# analogTCO-RJ-alone-ext.net
KiCad netlist of a schematic drawn in EAGLE
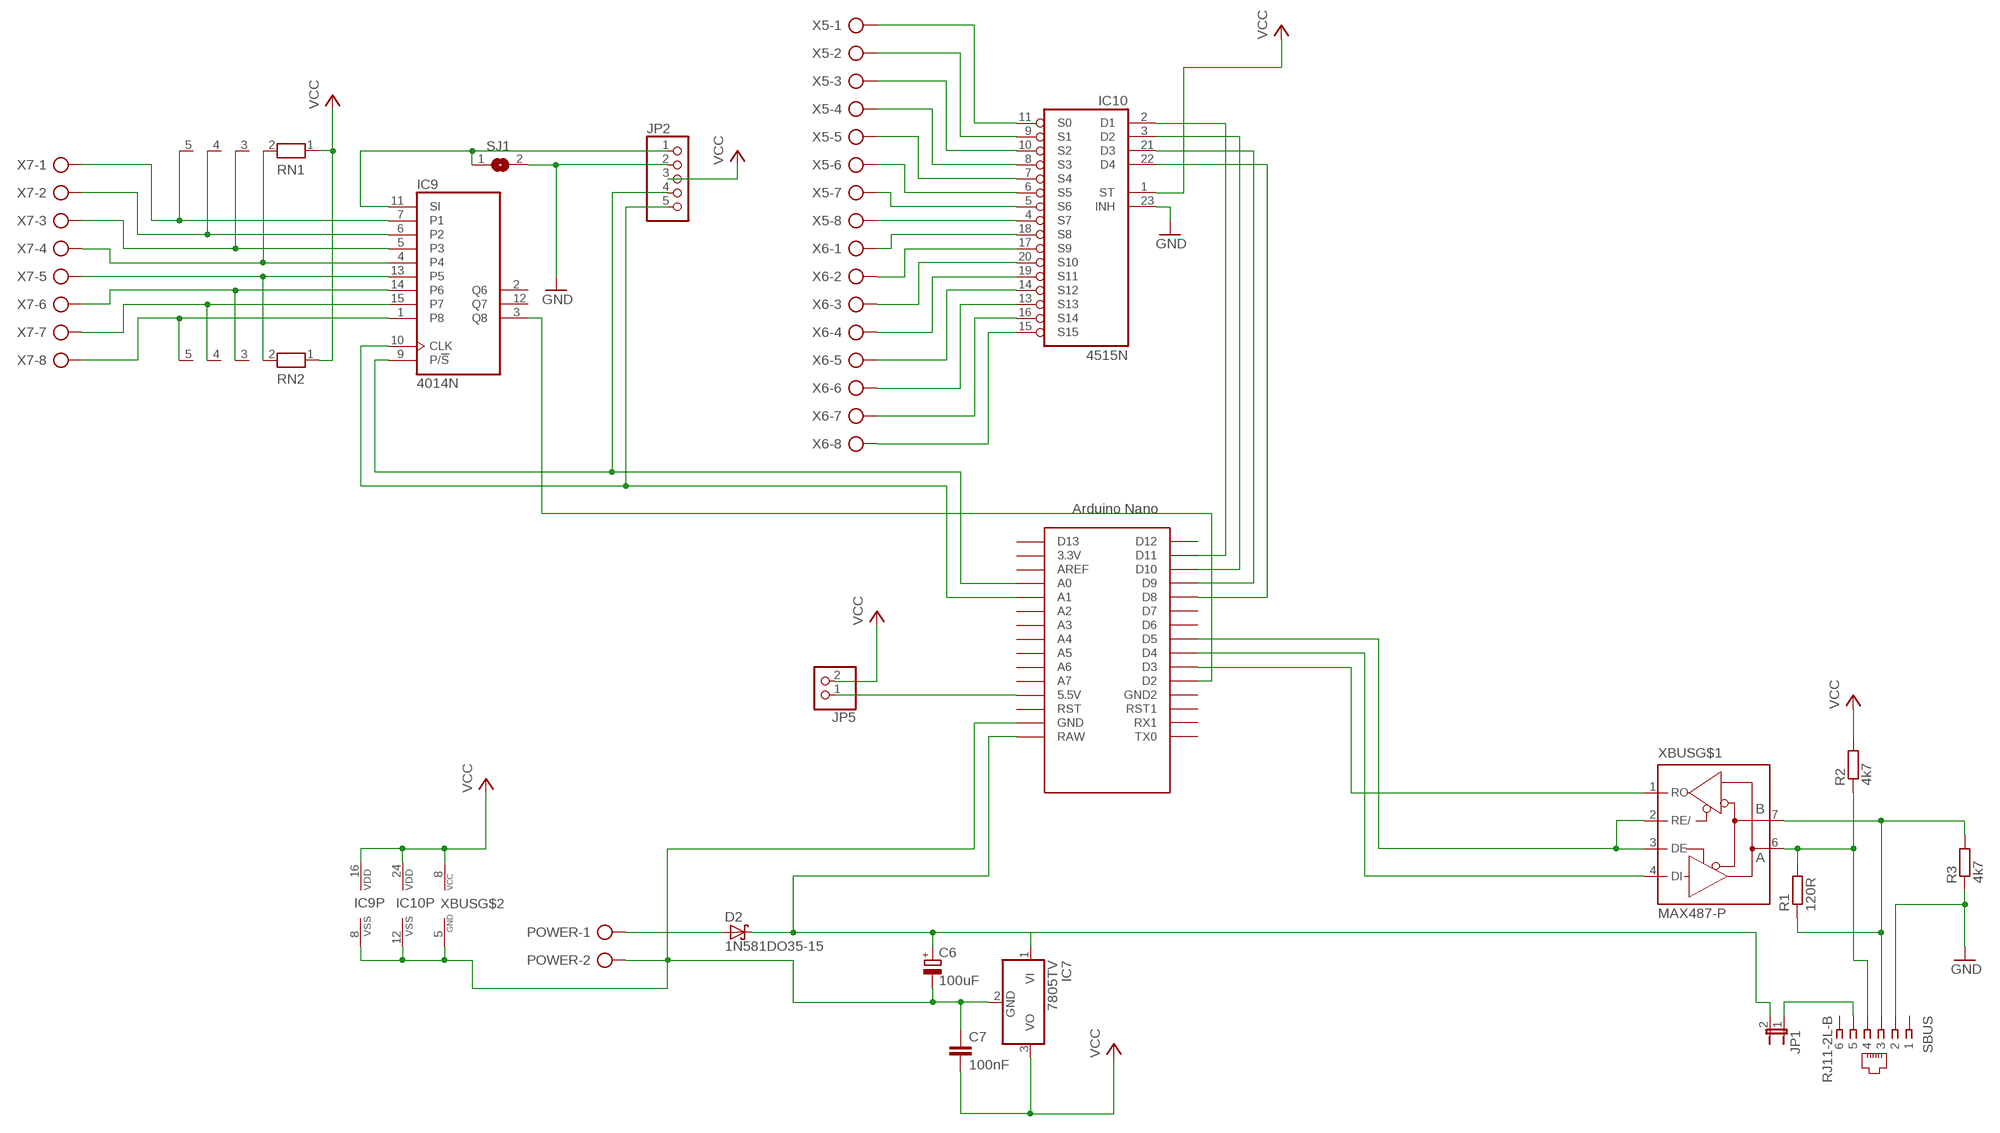
[diagram p0: schematic, sheet 1]

(export (version "E")
  (design (tool "Eeschema 10.0.6"))
  (components
    (comp (ref "C6")
      (value "100uF")
      (footprint "eagle-import:E2,5-6")
      (libsource (lib "eagle-import") (part "CPOL-EUE2.5-6"))
    )
    (comp (ref "C7")
      (value "100nF")
      (footprint "eagle-import:C025-025X050")
      (libsource (lib "eagle-import") (part "C-EU025-025X050"))
    )
    (comp (ref "D2")
      (value "1N581DO35-15")
      (footprint "eagle-import:DO35-10")
      (libsource (lib "eagle-import") (part "1N581DO35-15"))
    )
    (comp (ref "IC7")
      (value "7805TV")
      (footprint "eagle-import:TO220V")
      (libsource (lib "eagle-import") (part "78TV05"))
    )
    (comp (ref "IC9")
      (value "4014N")
      (footprint "eagle-import:DIL16")
      (libsource (lib "eagle-import") (part "4014N"))
    )
    (comp (ref "IC10")
      (value "4515N")
      (footprint "eagle-import:DIL24-6")
      (libsource (lib "eagle-import") (part "4515N"))
    )
    (comp (ref "JP1")
      (value "JP1E")
      (footprint "eagle-import:JP1")
      (libsource (lib "eagle-import") (part "JP1E"))
    )
    (comp (ref "JP2")
      (value "PINHD-1X5")
      (footprint "eagle-import:1X05")
      (libsource (lib "eagle-import") (part "PINHD-1X5"))
    )
    (comp (ref "JP5")
      (value "PINHD-1X2")
      (footprint "eagle-import:1X02")
      (libsource (lib "eagle-import") (part "PINHD-1X2"))
    )
    (comp (ref "POWER")
      (value "AK500/2")
      (footprint "eagle-import:AK500_2")
      (libsource (lib "eagle-import") (part "AK500/2"))
    )
    (comp (ref "R1")
      (value "120R")
      (footprint "eagle-import:0207_12")
      (libsource (lib "eagle-import") (part "R-EU_0207/12"))
    )
    (comp (ref "R2")
      (value "4k7")
      (footprint "eagle-import:0207_12")
      (libsource (lib "eagle-import") (part "R-EU_0207/12"))
    )
    (comp (ref "R3")
      (value "4k7")
      (footprint "eagle-import:0207_12")
      (libsource (lib "eagle-import") (part "R-EU_0207/12"))
    )
    (comp (ref "RN1")
      (value "RN04")
      (footprint "eagle-import:RN-5")
      (libsource (lib "eagle-import") (part "RN04"))
    )
    (comp (ref "RN2")
      (value "RN04")
      (footprint "eagle-import:RN-5")
      (libsource (lib "eagle-import") (part "RN04"))
    )
    (comp (ref "SBUS")
      (value "RJ11-2L-B")
      (footprint "eagle-import:RJ11-NO_SHIELD")
      (fields (field (name "MF") "TYCO ELECTRONICS"))
      (libsource (lib "eagle-import") (part "RJ11-2L-B"))
    )
    (comp (ref "SJ1") (value "SJ") (footprint "eagle-import:SJ") (libsource (lib "eagle-import") (part "SJ")))
    (comp (ref "U$1")
      (value "NANO")
      (footprint "eagle-import:NANO")
      (libsource (lib "eagle-import") (part "NANO"))
    )
    (comp (ref "X5")
      (value "AK500/8")
      (footprint "eagle-import:AK500_8")
      (libsource (lib "eagle-import") (part "AK500/8"))
    )
    (comp (ref "X6")
      (value "AK500/8")
      (footprint "eagle-import:AK500_8")
      (libsource (lib "eagle-import") (part "AK500/8"))
    )
    (comp (ref "X7")
      (value "AK500/8")
      (footprint "eagle-import:AK500_8")
      (libsource (lib "eagle-import") (part "AK500/8"))
    )
    (comp (ref "XBUS")
      (value "MAX487-P")
      (footprint "eagle-import:DIL08")
      (libsource (lib "eagle-import") (part "MAX487-P"))
    )
  )
  (nets
    (net (code "1") (name "GND") (class "Default")
      (node (ref "C6") (pin "-") (pinfunction "-_-") (pintype "passive"))
      (node (ref "C7") (pin "1") (pinfunction "1_1") (pintype "passive"))
      (node (ref "IC10") (pin "12") (pinfunction "VSS_12") (pintype "power_in"))
      (node (ref "IC10") (pin "23") (pinfunction "INH_23") (pintype "input"))
      (node (ref "IC7") (pin "2") (pinfunction "GND_2") (pintype "passive"))
      (node (ref "IC9") (pin "8") (pinfunction "VSS_8") (pintype "power_in"))
      (node (ref "JP2") (pin "2") (pinfunction "2_2") (pintype "passive"))
      (node (ref "POWER") (pin "2") (pinfunction "KL_2") (pintype "passive"))
      (node (ref "R3") (pin "1") (pinfunction "1_1") (pintype "passive"))
      (node (ref "SBUS") (pin "2") (pinfunction "2_2") (pintype "passive"))
      (node (ref "SJ1") (pin "2") (pinfunction "2_2") (pintype "passive"))
      (node (ref "U$1") (pin "GND") (pinfunction "GND_GND") (pintype "bidirectional"))
      (node (ref "XBUS") (pin "5") (pinfunction "GND_5") (pintype "power_in"))
    )
    (net (code "2") (name "Net-(IC7-VI)") (class "Default")
      (node (ref "C6") (pin "+") (pinfunction "+_+") (pintype "passive"))
      (node (ref "D2") (pin "C") (pinfunction "C_C") (pintype "passive"))
      (node (ref "IC7") (pin "1") (pinfunction "VI_1") (pintype "input"))
      (node (ref "JP1") (pin "2") (pinfunction "2_2") (pintype "passive"))
      (node (ref "U$1") (pin "RAW") (pinfunction "RAW_RAW") (pintype "bidirectional"))
    )
    (net (code "3") (name "Net-(IC9A-CLK)") (class "Default")
      (node (ref "IC9") (pin "10") (pinfunction "CLK_10") (pintype "input"))
      (node (ref "JP2") (pin "5") (pinfunction "5_5") (pintype "passive"))
      (node (ref "U$1") (pin "A1") (pinfunction "A1_A1") (pintype "bidirectional"))
    )
    (net (code "4") (name "Net-(IC9A-P1)") (class "Default")
      (node (ref "IC9") (pin "7") (pinfunction "P1_7") (pintype "input"))
      (node (ref "RN1") (pin "5") (pinfunction "5_5") (pintype "passive"))
      (node (ref "X7") (pin "1") (pinfunction "KL_1") (pintype "passive"))
    )
    (net (code "5") (name "Net-(IC9A-P2)") (class "Default")
      (node (ref "IC9") (pin "6") (pinfunction "P2_6") (pintype "input"))
      (node (ref "RN1") (pin "4") (pinfunction "4_4") (pintype "passive"))
      (node (ref "X7") (pin "2") (pinfunction "KL_2") (pintype "passive"))
    )
    (net (code "6") (name "Net-(IC9A-P3)") (class "Default")
      (node (ref "IC9") (pin "5") (pinfunction "P3_5") (pintype "input"))
      (node (ref "RN1") (pin "3") (pinfunction "3_3") (pintype "passive"))
      (node (ref "X7") (pin "3") (pinfunction "KL_3") (pintype "passive"))
    )
    (net (code "7") (name "Net-(IC9A-P4)") (class "Default")
      (node (ref "IC9") (pin "4") (pinfunction "P4_4") (pintype "input"))
      (node (ref "RN1") (pin "2") (pinfunction "2_2") (pintype "passive"))
      (node (ref "X7") (pin "4") (pinfunction "KL_4") (pintype "passive"))
    )
    (net (code "8") (name "Net-(IC9A-P5)") (class "Default")
      (node (ref "IC9") (pin "13") (pinfunction "P5_13") (pintype "input"))
      (node (ref "RN2") (pin "2") (pinfunction "2_2") (pintype "passive"))
      (node (ref "X7") (pin "5") (pinfunction "KL_5") (pintype "passive"))
    )
    (net (code "9") (name "Net-(IC9A-P6)") (class "Default")
      (node (ref "IC9") (pin "14") (pinfunction "P6_14") (pintype "input"))
      (node (ref "RN2") (pin "3") (pinfunction "3_3") (pintype "passive"))
      (node (ref "X7") (pin "6") (pinfunction "KL_6") (pintype "passive"))
    )
    (net (code "10") (name "Net-(IC9A-P7)") (class "Default")
      (node (ref "IC9") (pin "15") (pinfunction "P7_15") (pintype "input"))
      (node (ref "RN2") (pin "4") (pinfunction "4_4") (pintype "passive"))
      (node (ref "X7") (pin "7") (pinfunction "KL_7") (pintype "passive"))
    )
    (net (code "11") (name "Net-(IC9A-P8)") (class "Default")
      (node (ref "IC9") (pin "1") (pinfunction "P8_1") (pintype "input"))
      (node (ref "RN2") (pin "5") (pinfunction "5_5") (pintype "passive"))
      (node (ref "X7") (pin "8") (pinfunction "KL_8") (pintype "passive"))
    )
    (net (code "12") (name "Net-(IC9A-P{slash}~{S})") (class "Default")
      (node (ref "IC9") (pin "9") (pinfunction "P/~{S}_9") (pintype "input"))
      (node (ref "JP2") (pin "4") (pinfunction "4_4") (pintype "passive"))
      (node (ref "U$1") (pin "A0") (pinfunction "A0_A0") (pintype "bidirectional"))
    )
    (net (code "13") (name "Net-(IC9A-Q8)") (class "Default")
      (node (ref "IC9") (pin "3") (pinfunction "Q8_3") (pintype "output"))
      (node (ref "U$1") (pin "D2") (pinfunction "D2_D2") (pintype "bidirectional"))
    )
    (net (code "14") (name "Net-(IC9A-SI)") (class "Default")
      (node (ref "IC9") (pin "11") (pinfunction "SI_11") (pintype "input"))
      (node (ref "JP2") (pin "1") (pinfunction "1_1") (pintype "passive"))
      (node (ref "SJ1") (pin "1") (pinfunction "1_1") (pintype "passive"))
    )
    (net (code "15") (name "Net-(IC10A-D1)") (class "Default")
      (node (ref "IC10") (pin "2") (pinfunction "D1_2") (pintype "input"))
      (node (ref "U$1") (pin "D11") (pinfunction "D11_D11") (pintype "bidirectional"))
    )
    (net (code "16") (name "Net-(IC10A-D2)") (class "Default")
      (node (ref "IC10") (pin "3") (pinfunction "D2_3") (pintype "input"))
      (node (ref "U$1") (pin "D10") (pinfunction "D10_D10") (pintype "bidirectional"))
    )
    (net (code "17") (name "Net-(IC10A-D3)") (class "Default")
      (node (ref "IC10") (pin "21") (pinfunction "D3_21") (pintype "input"))
      (node (ref "U$1") (pin "D9") (pinfunction "D9_D9") (pintype "bidirectional"))
    )
    (net (code "18") (name "Net-(IC10A-D4)") (class "Default")
      (node (ref "IC10") (pin "22") (pinfunction "D4_22") (pintype "input"))
      (node (ref "U$1") (pin "D8") (pinfunction "D8_D8") (pintype "bidirectional"))
    )
    (net (code "19") (name "Net-(IC10A-S0)") (class "Default")
      (node (ref "IC10") (pin "11") (pinfunction "S0_11") (pintype "output"))
      (node (ref "X5") (pin "1") (pinfunction "KL_1") (pintype "passive"))
    )
    (net (code "20") (name "Net-(IC10A-S1)") (class "Default")
      (node (ref "IC10") (pin "9") (pinfunction "S1_9") (pintype "output"))
      (node (ref "X5") (pin "2") (pinfunction "KL_2") (pintype "passive"))
    )
    (net (code "21") (name "Net-(IC10A-S2)") (class "Default")
      (node (ref "IC10") (pin "10") (pinfunction "S2_10") (pintype "output"))
      (node (ref "X5") (pin "3") (pinfunction "KL_3") (pintype "passive"))
    )
    (net (code "22") (name "Net-(IC10A-S3)") (class "Default")
      (node (ref "IC10") (pin "8") (pinfunction "S3_8") (pintype "output"))
      (node (ref "X5") (pin "4") (pinfunction "KL_4") (pintype "passive"))
    )
    (net (code "23") (name "Net-(IC10A-S4)") (class "Default")
      (node (ref "IC10") (pin "7") (pinfunction "S4_7") (pintype "output"))
      (node (ref "X5") (pin "5") (pinfunction "KL_5") (pintype "passive"))
    )
    (net (code "24") (name "Net-(IC10A-S5)") (class "Default")
      (node (ref "IC10") (pin "6") (pinfunction "S5_6") (pintype "output"))
      (node (ref "X5") (pin "6") (pinfunction "KL_6") (pintype "passive"))
    )
    (net (code "25") (name "Net-(IC10A-S6)") (class "Default")
      (node (ref "IC10") (pin "5") (pinfunction "S6_5") (pintype "output"))
      (node (ref "X5") (pin "7") (pinfunction "KL_7") (pintype "passive"))
    )
    (net (code "26") (name "Net-(IC10A-S7)") (class "Default")
      (node (ref "IC10") (pin "4") (pinfunction "S7_4") (pintype "output"))
      (node (ref "X5") (pin "8") (pinfunction "KL_8") (pintype "passive"))
    )
    (net (code "27") (name "Net-(IC10A-S8)") (class "Default")
      (node (ref "IC10") (pin "18") (pinfunction "S8_18") (pintype "output"))
      (node (ref "X6") (pin "1") (pinfunction "KL_1") (pintype "passive"))
    )
    (net (code "28") (name "Net-(IC10A-S9)") (class "Default")
      (node (ref "IC10") (pin "17") (pinfunction "S9_17") (pintype "output"))
      (node (ref "X6") (pin "2") (pinfunction "KL_2") (pintype "passive"))
    )
    (net (code "29") (name "Net-(IC10A-S10)") (class "Default")
      (node (ref "IC10") (pin "20") (pinfunction "S10_20") (pintype "output"))
      (node (ref "X6") (pin "3") (pinfunction "KL_3") (pintype "passive"))
    )
    (net (code "30") (name "Net-(IC10A-S11)") (class "Default")
      (node (ref "IC10") (pin "19") (pinfunction "S11_19") (pintype "output"))
      (node (ref "X6") (pin "4") (pinfunction "KL_4") (pintype "passive"))
    )
    (net (code "31") (name "Net-(IC10A-S12)") (class "Default")
      (node (ref "IC10") (pin "14") (pinfunction "S12_14") (pintype "output"))
      (node (ref "X6") (pin "5") (pinfunction "KL_5") (pintype "passive"))
    )
    (net (code "32") (name "Net-(IC10A-S13)") (class "Default")
      (node (ref "IC10") (pin "13") (pinfunction "S13_13") (pintype "output"))
      (node (ref "X6") (pin "6") (pinfunction "KL_6") (pintype "passive"))
    )
    (net (code "33") (name "Net-(IC10A-S14)") (class "Default")
      (node (ref "IC10") (pin "16") (pinfunction "S14_16") (pintype "output"))
      (node (ref "X6") (pin "7") (pinfunction "KL_7") (pintype "passive"))
    )
    (net (code "34") (name "Net-(IC10A-S15)") (class "Default")
      (node (ref "IC10") (pin "15") (pinfunction "S15_15") (pintype "output"))
      (node (ref "X6") (pin "8") (pinfunction "KL_8") (pintype "passive"))
    )
    (net (code "35") (name "Net-(JP1-Pad1)") (class "Default")
      (node (ref "JP1") (pin "1") (pinfunction "1_1") (pintype "passive"))
      (node (ref "SBUS") (pin "5") (pinfunction "5_5") (pintype "passive"))
    )
    (net (code "36") (name "Net-(POWERA-KL)") (class "Default")
      (node (ref "D2") (pin "A") (pinfunction "A_A") (pintype "passive"))
      (node (ref "POWER") (pin "1") (pinfunction "KL_1") (pintype "passive"))
    )
    (net (code "37") (name "Net-(U$1-5.5V)") (class "Default")
      (node (ref "JP5") (pin "1") (pinfunction "1_1") (pintype "passive"))
      (node (ref "U$1") (pin "5V") (pinfunction "5.5V_5V") (pintype "bidirectional"))
    )
    (net (code "38") (name "Net-(XBUSA-A)") (class "Default")
      (node (ref "R1") (pin "2") (pinfunction "2_2") (pintype "passive"))
      (node (ref "R2") (pin "1") (pinfunction "1_1") (pintype "passive"))
      (node (ref "SBUS") (pin "4") (pinfunction "4_4") (pintype "passive"))
      (node (ref "XBUS") (pin "6") (pinfunction "A_6") (pintype "passive"))
    )
    (net (code "39") (name "Net-(XBUSA-B)") (class "Default")
      (node (ref "R1") (pin "1") (pinfunction "1_1") (pintype "passive"))
      (node (ref "R3") (pin "2") (pinfunction "2_2") (pintype "passive"))
      (node (ref "SBUS") (pin "3") (pinfunction "3_3") (pintype "passive"))
      (node (ref "XBUS") (pin "7") (pinfunction "B_7") (pintype "passive"))
    )
    (net (code "40") (name "Net-(XBUSA-DE)") (class "Default")
      (node (ref "U$1") (pin "D5") (pinfunction "D5_D5") (pintype "bidirectional"))
      (node (ref "XBUS") (pin "2") (pinfunction "RE/_2") (pintype "input"))
      (node (ref "XBUS") (pin "3") (pinfunction "DE_3") (pintype "input"))
    )
    (net (code "41") (name "Net-(XBUSA-DI)") (class "Default")
      (node (ref "U$1") (pin "D4") (pinfunction "D4_D4") (pintype "bidirectional"))
      (node (ref "XBUS") (pin "4") (pinfunction "DI_4") (pintype "input"))
    )
    (net (code "42") (name "Net-(XBUSA-RO)") (class "Default")
      (node (ref "U$1") (pin "D3") (pinfunction "D3_D3") (pintype "bidirectional"))
      (node (ref "XBUS") (pin "1") (pinfunction "RO_1") (pintype "output"))
    )
    (net (code "43") (name "VCC") (class "Default")
      (node (ref "C7") (pin "2") (pinfunction "2_2") (pintype "passive"))
      (node (ref "IC10") (pin "1") (pinfunction "ST_1") (pintype "input"))
      (node (ref "IC10") (pin "24") (pinfunction "VDD_24") (pintype "power_in"))
      (node (ref "IC7") (pin "3") (pinfunction "VO_3") (pintype "passive"))
      (node (ref "IC9") (pin "16") (pinfunction "VDD_16") (pintype "power_in"))
      (node (ref "JP2") (pin "3") (pinfunction "3_3") (pintype "passive"))
      (node (ref "JP5") (pin "2") (pinfunction "2_2") (pintype "passive"))
      (node (ref "R2") (pin "2") (pinfunction "2_2") (pintype "passive"))
      (node (ref "RN1") (pin "1") (pinfunction "1_1") (pintype "passive"))
      (node (ref "RN2") (pin "1") (pinfunction "1_1") (pintype "passive"))
      (node (ref "XBUS") (pin "8") (pinfunction "VCC_8") (pintype "power_in"))
    )
    (net (code "44") (name "unconnected-(IC9A-Q6-Pad2)") (class "Default")
      (node (ref "IC9") (pin "2") (pinfunction "Q6_2") (pintype "output"))
    )
    (net (code "45") (name "unconnected-(IC9A-Q7-Pad12)") (class "Default")
      (node (ref "IC9") (pin "12") (pinfunction "Q7_12") (pintype "output"))
    )
    (net (code "46") (name "unconnected-(SBUS-Pad1)") (class "Default")
      (node (ref "SBUS") (pin "1") (pinfunction "1_1") (pintype "passive"))
    )
    (net (code "47") (name "unconnected-(SBUS-Pad6)") (class "Default")
      (node (ref "SBUS") (pin "6") (pinfunction "6_6") (pintype "passive"))
    )
    (net (code "48") (name "unconnected-(U$1-GND2-PadGND1)") (class "Default")
      (node (ref "U$1") (pin "GND1") (pinfunction "GND2_GND1") (pintype "bidirectional"))
    )
    (net (code "49") (name "unconnected-(U$1-Pad3.3V)") (class "Default")
      (node (ref "U$1") (pin "3.3V") (pinfunction "3.3V_3.3V") (pintype "bidirectional"))
    )
    (net (code "50") (name "unconnected-(U$1-PadA2)") (class "Default")
      (node (ref "U$1") (pin "A2") (pinfunction "A2_A2") (pintype "bidirectional"))
    )
    (net (code "51") (name "unconnected-(U$1-PadA3)") (class "Default")
      (node (ref "U$1") (pin "A3") (pinfunction "A3_A3") (pintype "bidirectional"))
    )
    (net (code "52") (name "unconnected-(U$1-PadA4)") (class "Default")
      (node (ref "U$1") (pin "A4") (pinfunction "A4_A4") (pintype "bidirectional"))
    )
    (net (code "53") (name "unconnected-(U$1-PadA5)") (class "Default")
      (node (ref "U$1") (pin "A5") (pinfunction "A5_A5") (pintype "bidirectional"))
    )
    (net (code "54") (name "unconnected-(U$1-PadA6)") (class "Default")
      (node (ref "U$1") (pin "A6") (pinfunction "A6_A6") (pintype "bidirectional"))
    )
    (net (code "55") (name "unconnected-(U$1-PadA7)") (class "Default")
      (node (ref "U$1") (pin "A7") (pinfunction "A7_A7") (pintype "bidirectional"))
    )
    (net (code "56") (name "unconnected-(U$1-PadAREF)") (class "Default")
      (node (ref "U$1") (pin "AREF") (pinfunction "AREF_AREF") (pintype "bidirectional"))
    )
    (net (code "57") (name "unconnected-(U$1-PadD6)") (class "Default")
      (node (ref "U$1") (pin "D6") (pinfunction "D6_D6") (pintype "bidirectional"))
    )
    (net (code "58") (name "unconnected-(U$1-PadD7)") (class "Default")
      (node (ref "U$1") (pin "D7") (pinfunction "D7_D7") (pintype "bidirectional"))
    )
    (net (code "59") (name "unconnected-(U$1-PadD12)") (class "Default")
      (node (ref "U$1") (pin "D12") (pinfunction "D12_D12") (pintype "bidirectional"))
    )
    (net (code "60") (name "unconnected-(U$1-PadD13)") (class "Default")
      (node (ref "U$1") (pin "D13") (pinfunction "D13_D13") (pintype "bidirectional"))
    )
    (net (code "61") (name "unconnected-(U$1-PadICSP1)") (class "Default")
      (node (ref "U$1") (pin "ICSP1") (pinfunction "ICSP1_ICSP1") (pintype "bidirectional"))
    )
    (net (code "62") (name "unconnected-(U$1-PadICSP2)") (class "Default")
      (node (ref "U$1") (pin "ICSP2") (pinfunction "ICSP2_ICSP2") (pintype "bidirectional"))
    )
    (net (code "63") (name "unconnected-(U$1-PadICSP3)") (class "Default")
      (node (ref "U$1") (pin "ICSP3") (pinfunction "ICSP3_ICSP3") (pintype "bidirectional"))
    )
    (net (code "64") (name "unconnected-(U$1-PadICSP4)") (class "Default")
      (node (ref "U$1") (pin "ICSP4") (pinfunction "ICSP4_ICSP4") (pintype "bidirectional"))
    )
    (net (code "65") (name "unconnected-(U$1-PadICSP5)") (class "Default")
      (node (ref "U$1") (pin "ICSP5") (pinfunction "ICSP5_ICSP5") (pintype "bidirectional"))
    )
    (net (code "66") (name "unconnected-(U$1-PadICSP6)") (class "Default")
      (node (ref "U$1") (pin "ICSP6") (pinfunction "ICSP6_ICSP6") (pintype "bidirectional"))
    )
    (net (code "67") (name "unconnected-(U$1-PadRST)") (class "Default")
      (node (ref "U$1") (pin "RST") (pinfunction "RST_RST") (pintype "bidirectional"))
    )
    (net (code "68") (name "unconnected-(U$1-PadRST1)") (class "Default")
      (node (ref "U$1") (pin "RST1") (pinfunction "RST1_RST1") (pintype "bidirectional"))
    )
    (net (code "69") (name "unconnected-(U$1-PadRX1)") (class "Default")
      (node (ref "U$1") (pin "RX1") (pinfunction "RX1_RX1") (pintype "bidirectional"))
    )
    (net (code "70") (name "unconnected-(U$1-PadTX0)") (class "Default")
      (node (ref "U$1") (pin "TX0") (pinfunction "TX0_TX0") (pintype "bidirectional"))
    )
  )
)
